# ZX_UNO_Aplus_HAT1.net
KiCad netlist of a schematic drawn in Altium Designer
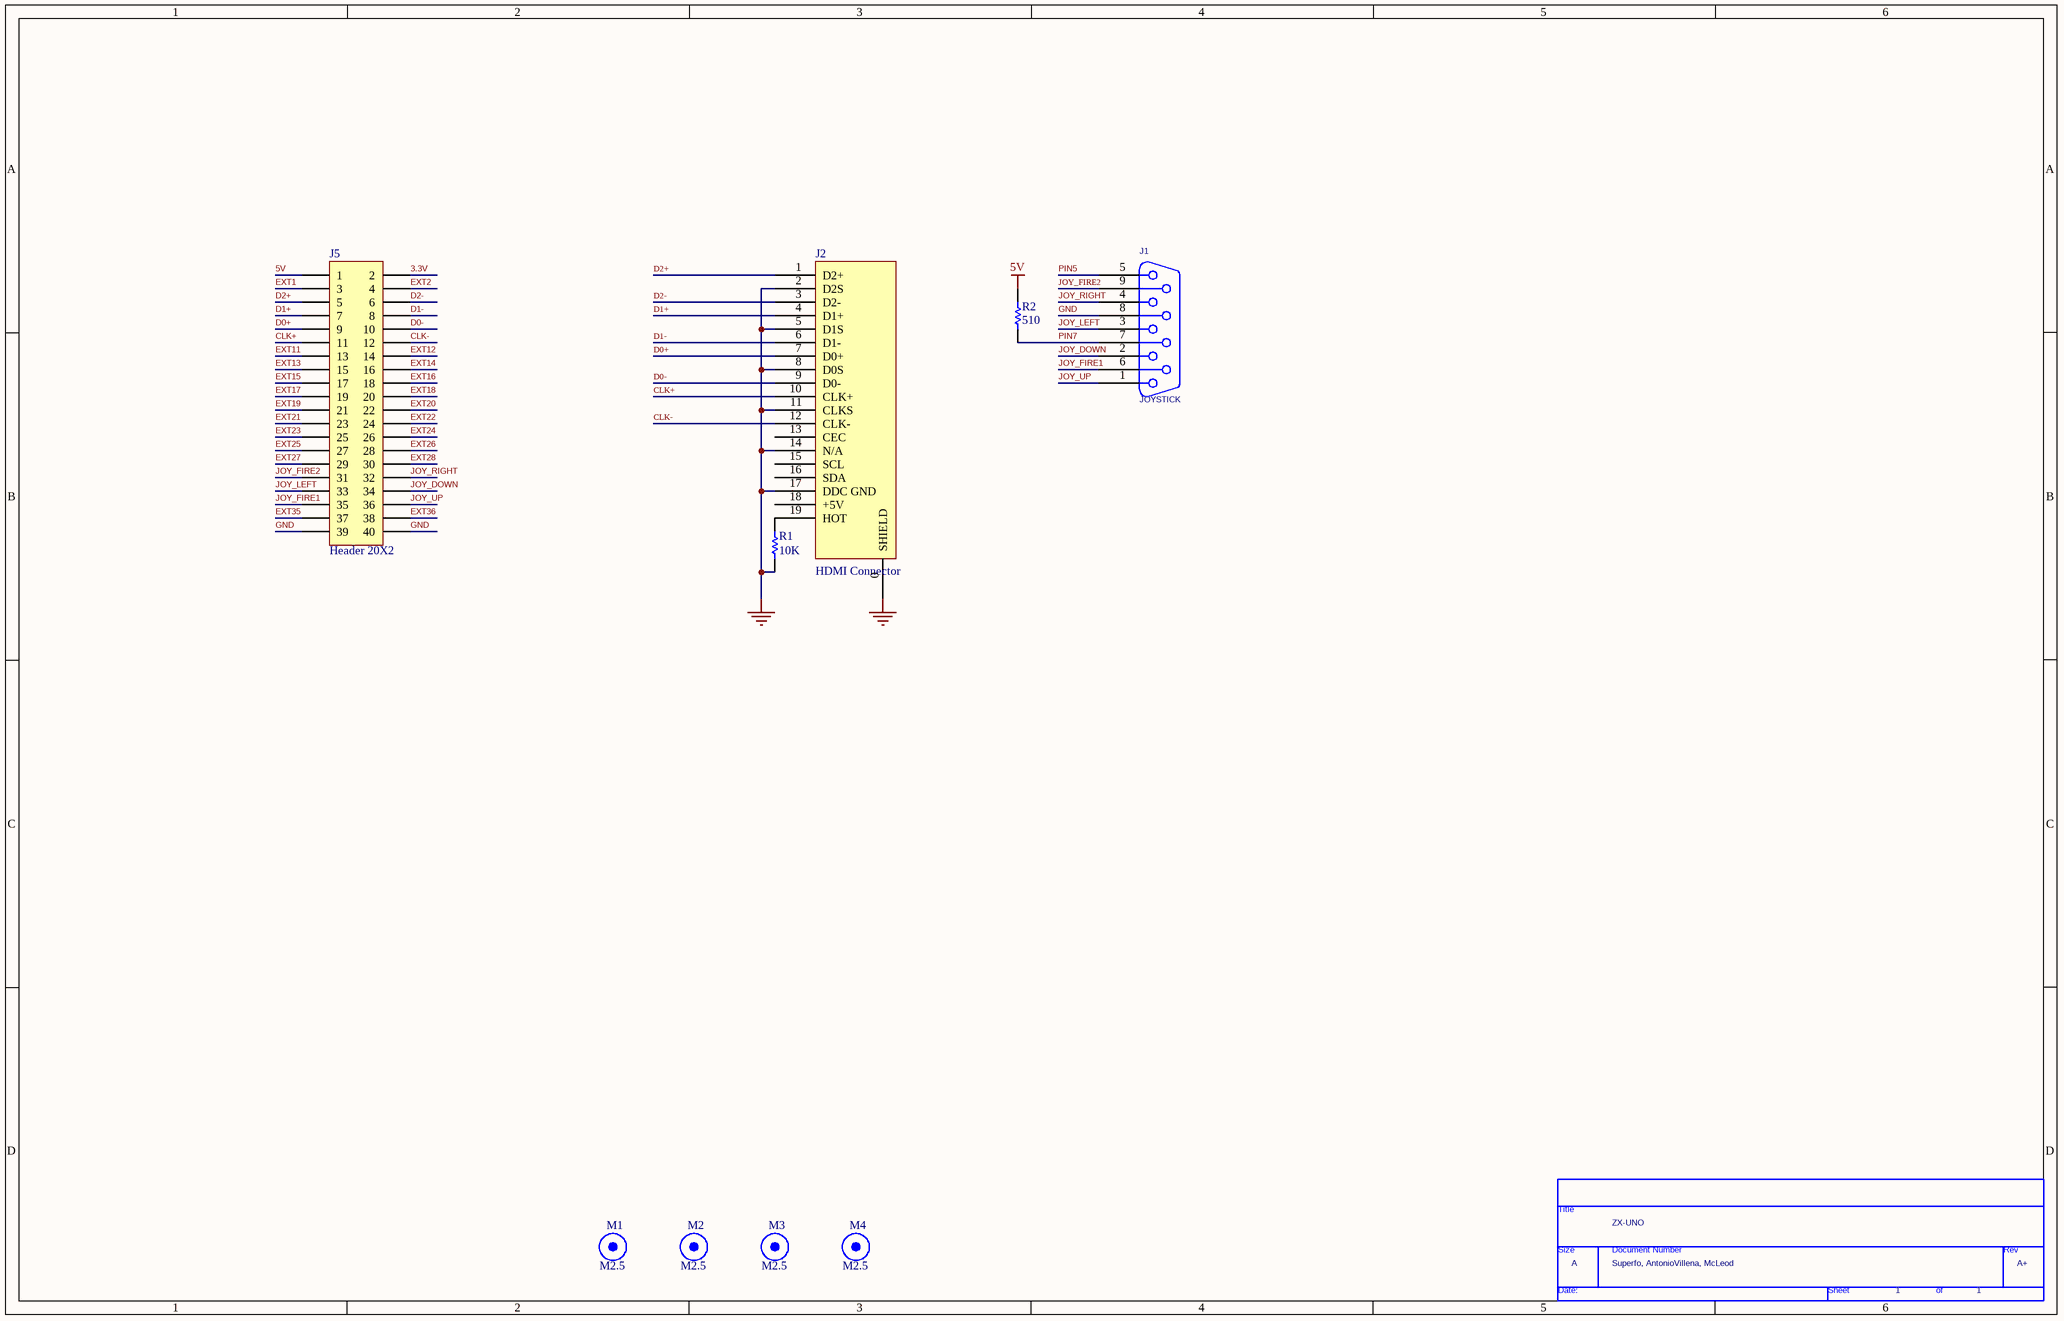
[diagram p0: ZX_UNO_Aplus_HAT1.SchDoc]

(export (version "E")
  (design (tool "Eeschema 10.0.6"))
  (components
    (comp (ref "*")
      (value "TitleBlock0")
      (fields
        (field (name "PAGE COUNT") "1")
        (field (name "PAGE NUMBER") "1")
        (field (name "PAGE SIZE") "A")
        (field (name "TITLE") "ZX-UNO")
        (field (name "REVCODE") "A+")
        (field (name "DOC") "Superfo, AntonioVillena, McLeod")
      )
      (libsource (lib "*") (part "TitleBlock0"))
    )
    (comp (ref "J1") (value "JOYSTICK") (libsource (lib "*") (part "CONNECTOR DB9")))
    (comp (ref "J2")
      (value "HDMI Connector")
      (footprint "HDMI 10029449")
      (description "HDMI, SMD, R/A KDMIX-NS1-WS-B")
      (libsource (lib "AltiumDesignLibrary") (part "HDMI-RA-Kycon"))
    )
    (comp (ref "J5")
      (value "Header 20X2")
      (footprint "HDR2X20")
      (description "Header, 20-Pin, Dual row")
      (fields (field (name "PUBLISHER") "Altium Limited"))
      (libsource (lib "Miscellaneous Connectors") (part "Header 20X2"))
    )
    (comp (ref "M1") (value "M2.5") (footprint "M2.5") (libsource (lib "Misc Devices 2") (part "M2.5")))
    (comp (ref "M2") (value "M2.5") (footprint "M2.5") (libsource (lib "Misc Devices 2") (part "M2.5")))
    (comp (ref "M3") (value "M2.5") (footprint "M2.5") (libsource (lib "Misc Devices 2") (part "M2.5")))
    (comp (ref "M4") (value "M2.5") (footprint "M2.5") (libsource (lib "Misc Devices 2") (part "M2.5")))
    (comp (ref "R1")
      (value "10K")
      (footprint "SM/R_0805")
      (description "Resistor")
      (fields (field (name "Comment") "Res1") (field (name "PUBLISHER") "Altium Limited"))
      (libsource (lib "Miscellaneous Devices") (part "Res1"))
    )
    (comp (ref "R2")
      (value "510")
      (footprint "SM/R_0805")
      (description "Resistor")
      (fields (field (name "Comment") "Res1") (field (name "PUBLISHER") "Altium Limited"))
      (libsource (lib "Miscellaneous Devices") (part "Res1"))
    )
  )
  (nets
    (net (code "1") (name "/3.3V") (class "Default")
      (node (ref "J5") (pin "2") (pinfunction "2_2") (pintype "passive"))
    )
    (net (code "2") (name "/CLK+") (class "Default")
      (node (ref "J2") (pin "10") (pinfunction "CLK+_10") (pintype "passive"))
      (node (ref "J5") (pin "11") (pinfunction "11_11") (pintype "passive"))
    )
    (net (code "3") (name "/CLK-") (class "Default")
      (node (ref "J2") (pin "12") (pinfunction "CLK-_12") (pintype "passive"))
      (node (ref "J5") (pin "12") (pinfunction "12_12") (pintype "passive"))
    )
    (net (code "4") (name "/D0+") (class "Default")
      (node (ref "J2") (pin "7") (pinfunction "D0+_7") (pintype "passive"))
      (node (ref "J5") (pin "9") (pinfunction "9_9") (pintype "passive"))
    )
    (net (code "5") (name "/D0-") (class "Default")
      (node (ref "J2") (pin "9") (pinfunction "D0-_9") (pintype "passive"))
      (node (ref "J5") (pin "10") (pinfunction "10_10") (pintype "passive"))
    )
    (net (code "6") (name "/D1+") (class "Default")
      (node (ref "J2") (pin "4") (pinfunction "D1+_4") (pintype "passive"))
      (node (ref "J5") (pin "7") (pinfunction "7_7") (pintype "passive"))
    )
    (net (code "7") (name "/D1-") (class "Default")
      (node (ref "J2") (pin "6") (pinfunction "D1-_6") (pintype "passive"))
      (node (ref "J5") (pin "8") (pinfunction "8_8") (pintype "passive"))
    )
    (net (code "8") (name "/D2+") (class "Default")
      (node (ref "J2") (pin "1") (pinfunction "D2+_1") (pintype "passive"))
      (node (ref "J5") (pin "5") (pinfunction "5_5") (pintype "passive"))
    )
    (net (code "9") (name "/D2-") (class "Default")
      (node (ref "J2") (pin "3") (pinfunction "D2-_3") (pintype "passive"))
      (node (ref "J5") (pin "6") (pinfunction "6_6") (pintype "passive"))
    )
    (net (code "10") (name "/EXT1") (class "Default")
      (node (ref "J5") (pin "3") (pinfunction "3_3") (pintype "passive"))
    )
    (net (code "11") (name "/EXT2") (class "Default")
      (node (ref "J5") (pin "4") (pinfunction "4_4") (pintype "passive"))
    )
    (net (code "12") (name "/EXT11") (class "Default")
      (node (ref "J5") (pin "13") (pinfunction "13_13") (pintype "passive"))
    )
    (net (code "13") (name "/EXT12") (class "Default")
      (node (ref "J5") (pin "14") (pinfunction "14_14") (pintype "passive"))
    )
    (net (code "14") (name "/EXT13") (class "Default")
      (node (ref "J5") (pin "15") (pinfunction "15_15") (pintype "passive"))
    )
    (net (code "15") (name "/EXT14") (class "Default")
      (node (ref "J5") (pin "16") (pinfunction "16_16") (pintype "passive"))
    )
    (net (code "16") (name "/EXT15") (class "Default")
      (node (ref "J5") (pin "17") (pinfunction "17_17") (pintype "passive"))
    )
    (net (code "17") (name "/EXT16") (class "Default")
      (node (ref "J5") (pin "18") (pinfunction "18_18") (pintype "passive"))
    )
    (net (code "18") (name "/EXT17") (class "Default")
      (node (ref "J5") (pin "19") (pinfunction "19_19") (pintype "passive"))
    )
    (net (code "19") (name "/EXT18") (class "Default")
      (node (ref "J5") (pin "20") (pinfunction "20_20") (pintype "passive"))
    )
    (net (code "20") (name "/EXT19") (class "Default")
      (node (ref "J5") (pin "21") (pinfunction "21_21") (pintype "passive"))
    )
    (net (code "21") (name "/EXT20") (class "Default")
      (node (ref "J5") (pin "22") (pinfunction "22_22") (pintype "passive"))
    )
    (net (code "22") (name "/EXT21") (class "Default")
      (node (ref "J5") (pin "23") (pinfunction "23_23") (pintype "passive"))
    )
    (net (code "23") (name "/EXT22") (class "Default")
      (node (ref "J5") (pin "24") (pinfunction "24_24") (pintype "passive"))
    )
    (net (code "24") (name "/EXT23") (class "Default")
      (node (ref "J5") (pin "25") (pinfunction "25_25") (pintype "passive"))
    )
    (net (code "25") (name "/EXT24") (class "Default")
      (node (ref "J5") (pin "26") (pinfunction "26_26") (pintype "passive"))
    )
    (net (code "26") (name "/EXT25") (class "Default")
      (node (ref "J5") (pin "27") (pinfunction "27_27") (pintype "passive"))
    )
    (net (code "27") (name "/EXT26") (class "Default")
      (node (ref "J5") (pin "28") (pinfunction "28_28") (pintype "passive"))
    )
    (net (code "28") (name "/EXT27") (class "Default")
      (node (ref "J5") (pin "29") (pinfunction "29_29") (pintype "passive"))
    )
    (net (code "29") (name "/EXT28") (class "Default")
      (node (ref "J5") (pin "30") (pinfunction "30_30") (pintype "passive"))
    )
    (net (code "30") (name "/EXT35") (class "Default")
      (node (ref "J5") (pin "37") (pinfunction "37_37") (pintype "passive"))
    )
    (net (code "31") (name "/EXT36") (class "Default")
      (node (ref "J5") (pin "38") (pinfunction "38_38") (pintype "passive"))
    )
    (net (code "32") (name "/JOY_DOWN") (class "Default")
      (node (ref "J1") (pin "2") (pinfunction "2_2") (pintype "passive"))
      (node (ref "J5") (pin "34") (pinfunction "34_34") (pintype "passive"))
    )
    (net (code "33") (name "/JOY_FIRE1") (class "Default")
      (node (ref "J1") (pin "6") (pinfunction "6_6") (pintype "passive"))
      (node (ref "J5") (pin "35") (pinfunction "35_35") (pintype "passive"))
    )
    (net (code "34") (name "/JOY_FIRE2") (class "Default")
      (node (ref "J1") (pin "9") (pinfunction "9_9") (pintype "passive"))
      (node (ref "J5") (pin "31") (pinfunction "31_31") (pintype "passive"))
    )
    (net (code "35") (name "/JOY_LEFT") (class "Default")
      (node (ref "J1") (pin "3") (pinfunction "3_3") (pintype "passive"))
      (node (ref "J5") (pin "33") (pinfunction "33_33") (pintype "passive"))
    )
    (net (code "36") (name "/JOY_RIGHT") (class "Default")
      (node (ref "J1") (pin "4") (pinfunction "4_4") (pintype "passive"))
      (node (ref "J5") (pin "32") (pinfunction "32_32") (pintype "passive"))
    )
    (net (code "37") (name "/JOY_UP") (class "Default")
      (node (ref "J1") (pin "1") (pinfunction "1_1") (pintype "passive"))
      (node (ref "J5") (pin "36") (pinfunction "36_36") (pintype "passive"))
    )
    (net (code "38") (name "/PIN5") (class "Default")
      (node (ref "J1") (pin "5") (pinfunction "5_5") (pintype "passive"))
    )
    (net (code "39") (name "/PIN7") (class "Default")
      (node (ref "J1") (pin "7") (pinfunction "7_7") (pintype "passive"))
      (node (ref "R2") (pin "1") (pinfunction "1_1") (pintype "passive"))
    )
    (net (code "40") (name "5V") (class "Default")
      (node (ref "J5") (pin "1") (pinfunction "1_1") (pintype "passive"))
      (node (ref "R2") (pin "2") (pinfunction "2_2") (pintype "passive"))
    )
    (net (code "41") (name "GND") (class "Default")
      (node (ref "J1") (pin "8") (pinfunction "8_8") (pintype "passive"))
      (node (ref "J2") (pin "0") (pinfunction "SHIELD_0") (pintype "passive"))
      (node (ref "J2") (pin "11") (pinfunction "CLKS_11") (pintype "passive"))
      (node (ref "J2") (pin "14") (pinfunction "N/A_14") (pintype "passive"))
      (node (ref "J2") (pin "17") (pinfunction "DDC_GND_17") (pintype "passive"))
      (node (ref "J2") (pin "2") (pinfunction "D2S_2") (pintype "passive"))
      (node (ref "J2") (pin "5") (pinfunction "D1S_5") (pintype "passive"))
      (node (ref "J2") (pin "8") (pinfunction "D0S_8") (pintype "passive"))
      (node (ref "J5") (pin "39") (pinfunction "39_39") (pintype "passive"))
      (node (ref "J5") (pin "40") (pinfunction "40_40") (pintype "passive"))
      (node (ref "R1") (pin "1") (pinfunction "1_1") (pintype "passive"))
    )
    (net (code "42") (name "Net-(J2-HOT)") (class "Default")
      (node (ref "J2") (pin "19") (pinfunction "HOT_19") (pintype "passive"))
      (node (ref "R1") (pin "2") (pinfunction "2_2") (pintype "passive"))
    )
    (net (code "43") (name "unconnected-(J2-+5V-Pad18)") (class "Default")
      (node (ref "J2") (pin "18") (pinfunction "+5V_18") (pintype "passive"))
    )
    (net (code "44") (name "unconnected-(J2-CEC-Pad13)") (class "Default")
      (node (ref "J2") (pin "13") (pinfunction "CEC_13") (pintype "passive"))
    )
    (net (code "45") (name "unconnected-(J2-SCL-Pad15)") (class "Default")
      (node (ref "J2") (pin "15") (pinfunction "SCL_15") (pintype "passive"))
    )
    (net (code "46") (name "unconnected-(J2-SDA-Pad16)") (class "Default")
      (node (ref "J2") (pin "16") (pinfunction "SDA_16") (pintype "passive"))
    )
  )
)
